# Aidan_Macro_Pad.net
KiCad netlist of a schematic drawn in Altium Designer
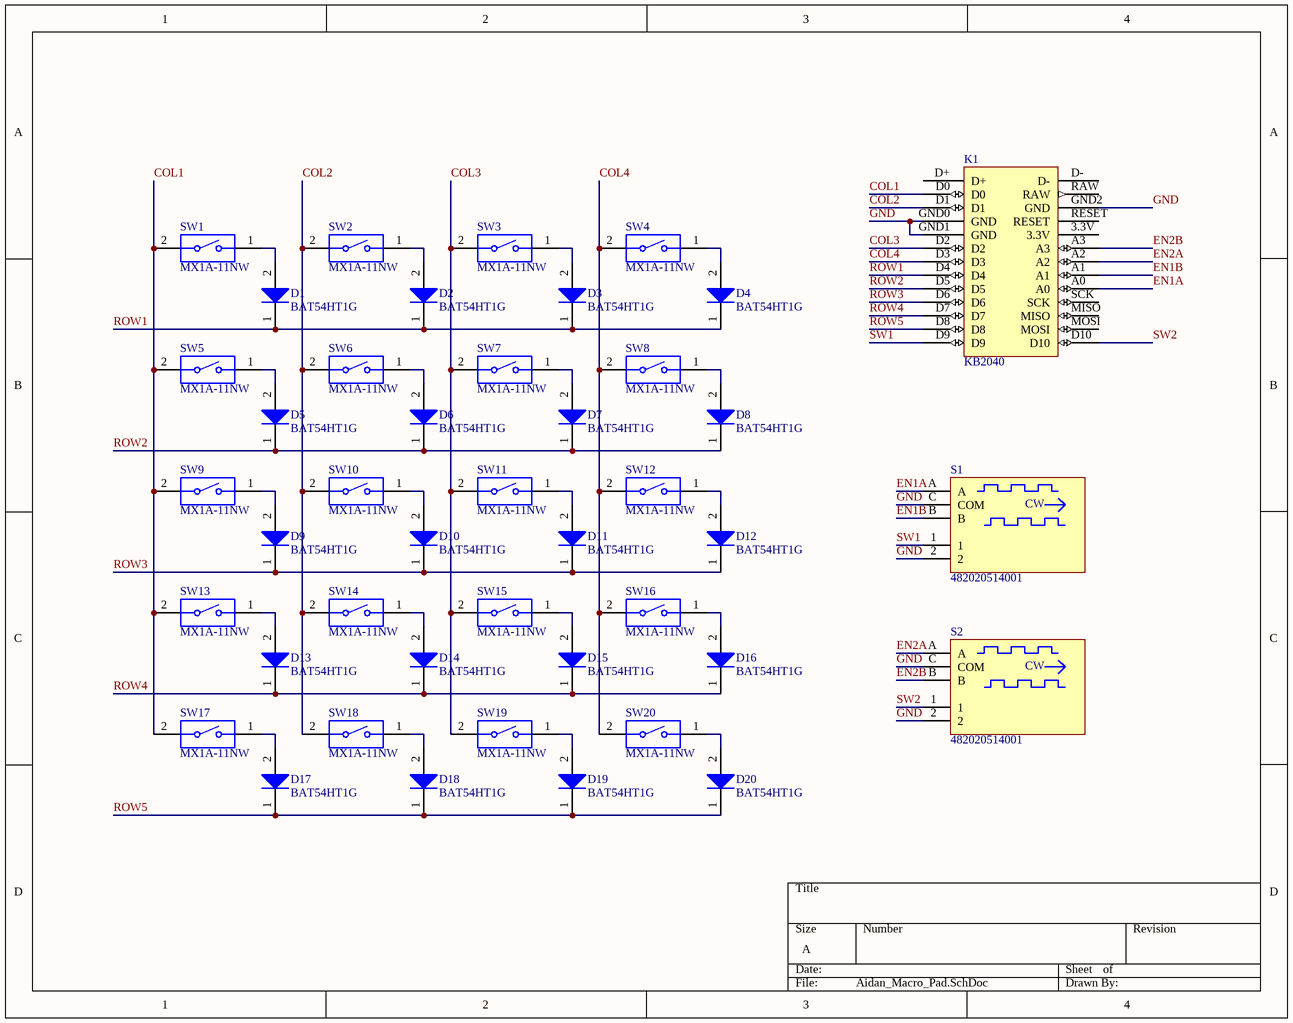
[diagram p0: Aidan_Macro_Pad.SchDoc]

(export (version "E")
  (design (tool "Eeschema 10.0.6"))
  (components
    (comp (ref "D1")
      (value "BAT54HT1G")
      (footprint "ONSC-SOD-323-2-477-02_V")
      (description "Rectifier Diode, 1 Phase, 1 Element, 0.2A, 30V V(RRM), Silicon")
      (libsource (lib "Aidan's Workspace") (part "ONSC-D-K1A2-2"))
    )
    (comp (ref "D2")
      (value "BAT54HT1G")
      (footprint "ONSC-SOD-323-2-477-02_V")
      (description "Rectifier Diode, 1 Phase, 1 Element, 0.2A, 30V V(RRM), Silicon")
      (libsource (lib "Aidan's Workspace") (part "ONSC-D-K1A2-2"))
    )
    (comp (ref "D3")
      (value "BAT54HT1G")
      (footprint "ONSC-SOD-323-2-477-02_V")
      (description "Rectifier Diode, 1 Phase, 1 Element, 0.2A, 30V V(RRM), Silicon")
      (libsource (lib "Aidan's Workspace") (part "ONSC-D-K1A2-2"))
    )
    (comp (ref "D4")
      (value "BAT54HT1G")
      (footprint "ONSC-SOD-323-2-477-02_V")
      (description "Rectifier Diode, 1 Phase, 1 Element, 0.2A, 30V V(RRM), Silicon")
      (libsource (lib "Aidan's Workspace") (part "ONSC-D-K1A2-2"))
    )
    (comp (ref "D5")
      (value "BAT54HT1G")
      (footprint "ONSC-SOD-323-2-477-02_V")
      (description "Rectifier Diode, 1 Phase, 1 Element, 0.2A, 30V V(RRM), Silicon")
      (libsource (lib "Aidan's Workspace") (part "ONSC-D-K1A2-2"))
    )
    (comp (ref "D6")
      (value "BAT54HT1G")
      (footprint "ONSC-SOD-323-2-477-02_V")
      (description "Rectifier Diode, 1 Phase, 1 Element, 0.2A, 30V V(RRM), Silicon")
      (libsource (lib "Aidan's Workspace") (part "ONSC-D-K1A2-2"))
    )
    (comp (ref "D7")
      (value "BAT54HT1G")
      (footprint "ONSC-SOD-323-2-477-02_V")
      (description "Rectifier Diode, 1 Phase, 1 Element, 0.2A, 30V V(RRM), Silicon")
      (libsource (lib "Aidan's Workspace") (part "ONSC-D-K1A2-2"))
    )
    (comp (ref "D8")
      (value "BAT54HT1G")
      (footprint "ONSC-SOD-323-2-477-02_V")
      (description "Rectifier Diode, 1 Phase, 1 Element, 0.2A, 30V V(RRM), Silicon")
      (libsource (lib "Aidan's Workspace") (part "ONSC-D-K1A2-2"))
    )
    (comp (ref "D9")
      (value "BAT54HT1G")
      (footprint "ONSC-SOD-323-2-477-02_V")
      (description "Rectifier Diode, 1 Phase, 1 Element, 0.2A, 30V V(RRM), Silicon")
      (libsource (lib "Aidan's Workspace") (part "ONSC-D-K1A2-2"))
    )
    (comp (ref "D10")
      (value "BAT54HT1G")
      (footprint "ONSC-SOD-323-2-477-02_V")
      (description "Rectifier Diode, 1 Phase, 1 Element, 0.2A, 30V V(RRM), Silicon")
      (libsource (lib "Aidan's Workspace") (part "ONSC-D-K1A2-2"))
    )
    (comp (ref "D11")
      (value "BAT54HT1G")
      (footprint "ONSC-SOD-323-2-477-02_V")
      (description "Rectifier Diode, 1 Phase, 1 Element, 0.2A, 30V V(RRM), Silicon")
      (libsource (lib "Aidan's Workspace") (part "ONSC-D-K1A2-2"))
    )
    (comp (ref "D12")
      (value "BAT54HT1G")
      (footprint "ONSC-SOD-323-2-477-02_V")
      (description "Rectifier Diode, 1 Phase, 1 Element, 0.2A, 30V V(RRM), Silicon")
      (libsource (lib "Aidan's Workspace") (part "ONSC-D-K1A2-2"))
    )
    (comp (ref "D13")
      (value "BAT54HT1G")
      (footprint "ONSC-SOD-323-2-477-02_V")
      (description "Rectifier Diode, 1 Phase, 1 Element, 0.2A, 30V V(RRM), Silicon")
      (libsource (lib "Aidan's Workspace") (part "ONSC-D-K1A2-2"))
    )
    (comp (ref "D14")
      (value "BAT54HT1G")
      (footprint "ONSC-SOD-323-2-477-02_V")
      (description "Rectifier Diode, 1 Phase, 1 Element, 0.2A, 30V V(RRM), Silicon")
      (libsource (lib "Aidan's Workspace") (part "ONSC-D-K1A2-2"))
    )
    (comp (ref "D15")
      (value "BAT54HT1G")
      (footprint "ONSC-SOD-323-2-477-02_V")
      (description "Rectifier Diode, 1 Phase, 1 Element, 0.2A, 30V V(RRM), Silicon")
      (libsource (lib "Aidan's Workspace") (part "ONSC-D-K1A2-2"))
    )
    (comp (ref "D16")
      (value "BAT54HT1G")
      (footprint "ONSC-SOD-323-2-477-02_V")
      (description "Rectifier Diode, 1 Phase, 1 Element, 0.2A, 30V V(RRM), Silicon")
      (libsource (lib "Aidan's Workspace") (part "ONSC-D-K1A2-2"))
    )
    (comp (ref "D17")
      (value "BAT54HT1G")
      (footprint "ONSC-SOD-323-2-477-02_V")
      (description "Rectifier Diode, 1 Phase, 1 Element, 0.2A, 30V V(RRM), Silicon")
      (libsource (lib "Aidan's Workspace") (part "ONSC-D-K1A2-2"))
    )
    (comp (ref "D18")
      (value "BAT54HT1G")
      (footprint "ONSC-SOD-323-2-477-02_V")
      (description "Rectifier Diode, 1 Phase, 1 Element, 0.2A, 30V V(RRM), Silicon")
      (libsource (lib "Aidan's Workspace") (part "ONSC-D-K1A2-2"))
    )
    (comp (ref "D19")
      (value "BAT54HT1G")
      (footprint "ONSC-SOD-323-2-477-02_V")
      (description "Rectifier Diode, 1 Phase, 1 Element, 0.2A, 30V V(RRM), Silicon")
      (libsource (lib "Aidan's Workspace") (part "ONSC-D-K1A2-2"))
    )
    (comp (ref "D20")
      (value "BAT54HT1G")
      (footprint "ONSC-SOD-323-2-477-02_V")
      (description "Rectifier Diode, 1 Phase, 1 Element, 0.2A, 30V V(RRM), Silicon")
      (libsource (lib "Aidan's Workspace") (part "ONSC-D-K1A2-2"))
    )
    (comp (ref "K1")
      (value "KB2040")
      (footprint "KB2040 Footprint")
      (description "Keyboard driver")
      (libsource (lib "Aidan's Workspace") (part "KB2040 Symbol"))
    )
    (comp (ref "S1")
      (value "482020514001")
      (footprint "4820xx514001")
      (description "Rotary Position Encoder")
      (libsource (lib "Aidan's Workspace") (part "Encoder Switch"))
    )
    (comp (ref "S2")
      (value "482020514001")
      (footprint "4820xx514001")
      (description "Rotary Position Encoder")
      (libsource (lib "Aidan's Workspace") (part "Encoder Switch"))
    )
    (comp (ref "SW1")
      (value "MX1A-11NW")
      (footprint "CHRY-MX1A-11NW_V")
      (libsource (lib "Aidan's Workspace") (part "KEYSW-SPST-2"))
    )
    (comp (ref "SW2")
      (value "MX1A-11NW")
      (footprint "CHRY-MX1A-11NW_V")
      (libsource (lib "Aidan's Workspace") (part "KEYSW-SPST-2"))
    )
    (comp (ref "SW3")
      (value "MX1A-11NW")
      (footprint "CHRY-MX1A-11NW_V")
      (libsource (lib "Aidan's Workspace") (part "KEYSW-SPST-2"))
    )
    (comp (ref "SW4")
      (value "MX1A-11NW")
      (footprint "CHRY-MX1A-11NW_V")
      (libsource (lib "Aidan's Workspace") (part "KEYSW-SPST-2"))
    )
    (comp (ref "SW5")
      (value "MX1A-11NW")
      (footprint "CHRY-MX1A-11NW_V")
      (libsource (lib "Aidan's Workspace") (part "KEYSW-SPST-2"))
    )
    (comp (ref "SW6")
      (value "MX1A-11NW")
      (footprint "CHRY-MX1A-11NW_V")
      (libsource (lib "Aidan's Workspace") (part "KEYSW-SPST-2"))
    )
    (comp (ref "SW7")
      (value "MX1A-11NW")
      (footprint "CHRY-MX1A-11NW_V")
      (libsource (lib "Aidan's Workspace") (part "KEYSW-SPST-2"))
    )
    (comp (ref "SW8")
      (value "MX1A-11NW")
      (footprint "CHRY-MX1A-11NW_V")
      (libsource (lib "Aidan's Workspace") (part "KEYSW-SPST-2"))
    )
    (comp (ref "SW9")
      (value "MX1A-11NW")
      (footprint "CHRY-MX1A-11NW_V")
      (libsource (lib "Aidan's Workspace") (part "KEYSW-SPST-2"))
    )
    (comp (ref "SW10")
      (value "MX1A-11NW")
      (footprint "CHRY-MX1A-11NW_V")
      (libsource (lib "Aidan's Workspace") (part "KEYSW-SPST-2"))
    )
    (comp (ref "SW11")
      (value "MX1A-11NW")
      (footprint "CHRY-MX1A-11NW_V")
      (libsource (lib "Aidan's Workspace") (part "KEYSW-SPST-2"))
    )
    (comp (ref "SW12")
      (value "MX1A-11NW")
      (footprint "CHRY-MX1A-11NW_V")
      (libsource (lib "Aidan's Workspace") (part "KEYSW-SPST-2"))
    )
    (comp (ref "SW13")
      (value "MX1A-11NW")
      (footprint "CHRY-MX1A-11NW_V")
      (libsource (lib "Aidan's Workspace") (part "KEYSW-SPST-2"))
    )
    (comp (ref "SW14")
      (value "MX1A-11NW")
      (footprint "CHRY-MX1A-11NW_V")
      (libsource (lib "Aidan's Workspace") (part "KEYSW-SPST-2"))
    )
    (comp (ref "SW15")
      (value "MX1A-11NW")
      (footprint "CHRY-MX1A-11NW_V")
      (libsource (lib "Aidan's Workspace") (part "KEYSW-SPST-2"))
    )
    (comp (ref "SW16")
      (value "MX1A-11NW")
      (footprint "CHRY-MX1A-11NW_V")
      (libsource (lib "Aidan's Workspace") (part "KEYSW-SPST-2"))
    )
    (comp (ref "SW17")
      (value "MX1A-11NW")
      (footprint "CHRY-MX1A-11NW_V")
      (libsource (lib "Aidan's Workspace") (part "KEYSW-SPST-2"))
    )
    (comp (ref "SW18")
      (value "MX1A-11NW")
      (footprint "CHRY-MX1A-11NW_V")
      (libsource (lib "Aidan's Workspace") (part "KEYSW-SPST-2"))
    )
    (comp (ref "SW19")
      (value "MX1A-11NW")
      (footprint "CHRY-MX1A-11NW_V")
      (libsource (lib "Aidan's Workspace") (part "KEYSW-SPST-2"))
    )
    (comp (ref "SW20")
      (value "MX1A-11NW")
      (footprint "CHRY-MX1A-11NW_V")
      (libsource (lib "Aidan's Workspace") (part "KEYSW-SPST-2"))
    )
  )
  (nets
    (net (code "1") (name "/COL1") (class "Default")
      (node (ref "K1") (pin "D0") (pinfunction "D0_D0") (pintype "bidirectional"))
      (node (ref "SW1") (pin "2") (pinfunction "2_2") (pintype "passive"))
      (node (ref "SW13") (pin "2") (pinfunction "2_2") (pintype "passive"))
      (node (ref "SW17") (pin "2") (pinfunction "2_2") (pintype "passive"))
      (node (ref "SW5") (pin "2") (pinfunction "2_2") (pintype "passive"))
      (node (ref "SW9") (pin "2") (pinfunction "2_2") (pintype "passive"))
    )
    (net (code "2") (name "/COL2") (class "Default")
      (node (ref "K1") (pin "D1") (pinfunction "D1_D1") (pintype "bidirectional"))
      (node (ref "SW10") (pin "2") (pinfunction "2_2") (pintype "passive"))
      (node (ref "SW14") (pin "2") (pinfunction "2_2") (pintype "passive"))
      (node (ref "SW18") (pin "2") (pinfunction "2_2") (pintype "passive"))
      (node (ref "SW2") (pin "2") (pinfunction "2_2") (pintype "passive"))
      (node (ref "SW6") (pin "2") (pinfunction "2_2") (pintype "passive"))
    )
    (net (code "3") (name "/COL3") (class "Default")
      (node (ref "K1") (pin "D2") (pinfunction "D2_D2") (pintype "bidirectional"))
      (node (ref "SW11") (pin "2") (pinfunction "2_2") (pintype "passive"))
      (node (ref "SW15") (pin "2") (pinfunction "2_2") (pintype "passive"))
      (node (ref "SW19") (pin "2") (pinfunction "2_2") (pintype "passive"))
      (node (ref "SW3") (pin "2") (pinfunction "2_2") (pintype "passive"))
      (node (ref "SW7") (pin "2") (pinfunction "2_2") (pintype "passive"))
    )
    (net (code "4") (name "/COL4") (class "Default")
      (node (ref "K1") (pin "D3") (pinfunction "D3_D3") (pintype "bidirectional"))
      (node (ref "SW12") (pin "2") (pinfunction "2_2") (pintype "passive"))
      (node (ref "SW16") (pin "2") (pinfunction "2_2") (pintype "passive"))
      (node (ref "SW20") (pin "2") (pinfunction "2_2") (pintype "passive"))
      (node (ref "SW4") (pin "2") (pinfunction "2_2") (pintype "passive"))
      (node (ref "SW8") (pin "2") (pinfunction "2_2") (pintype "passive"))
    )
    (net (code "5") (name "/EN1A") (class "Default")
      (node (ref "K1") (pin "A0") (pinfunction "A0_A0") (pintype "bidirectional"))
      (node (ref "S1") (pin "A") (pinfunction "A_A") (pintype "passive"))
    )
    (net (code "6") (name "/EN1B") (class "Default")
      (node (ref "K1") (pin "A1") (pinfunction "A1_A1") (pintype "bidirectional"))
      (node (ref "S1") (pin "B") (pinfunction "B_B") (pintype "passive"))
    )
    (net (code "7") (name "/EN2A") (class "Default")
      (node (ref "K1") (pin "A2") (pinfunction "A2_A2") (pintype "bidirectional"))
      (node (ref "S2") (pin "A") (pinfunction "A_A") (pintype "passive"))
    )
    (net (code "8") (name "/EN2B") (class "Default")
      (node (ref "K1") (pin "A3") (pinfunction "A3_A3") (pintype "bidirectional"))
      (node (ref "S2") (pin "B") (pinfunction "B_B") (pintype "passive"))
    )
    (net (code "9") (name "/GND") (class "Default")
      (node (ref "K1") (pin "GND0") (pinfunction "GND_GND0") (pintype "power_in"))
      (node (ref "K1") (pin "GND1") (pinfunction "GND_GND1") (pintype "power_in"))
      (node (ref "K1") (pin "GND2") (pinfunction "GND_GND2") (pintype "power_in"))
      (node (ref "S1") (pin "2") (pinfunction "2_2") (pintype "passive"))
      (node (ref "S1") (pin "C") (pinfunction "COM_C") (pintype "passive"))
      (node (ref "S2") (pin "2") (pinfunction "2_2") (pintype "passive"))
      (node (ref "S2") (pin "C") (pinfunction "COM_C") (pintype "passive"))
    )
    (net (code "10") (name "/ROW1") (class "Default")
      (node (ref "D1") (pin "1") (pinfunction "K_1") (pintype "passive"))
      (node (ref "D2") (pin "1") (pinfunction "K_1") (pintype "passive"))
      (node (ref "D3") (pin "1") (pinfunction "K_1") (pintype "passive"))
      (node (ref "D4") (pin "1") (pinfunction "K_1") (pintype "passive"))
      (node (ref "K1") (pin "D4") (pinfunction "D4_D4") (pintype "bidirectional"))
    )
    (net (code "11") (name "/ROW2") (class "Default")
      (node (ref "D5") (pin "1") (pinfunction "K_1") (pintype "passive"))
      (node (ref "D6") (pin "1") (pinfunction "K_1") (pintype "passive"))
      (node (ref "D7") (pin "1") (pinfunction "K_1") (pintype "passive"))
      (node (ref "D8") (pin "1") (pinfunction "K_1") (pintype "passive"))
      (node (ref "K1") (pin "D5") (pinfunction "D5_D5") (pintype "bidirectional"))
    )
    (net (code "12") (name "/ROW3") (class "Default")
      (node (ref "D10") (pin "1") (pinfunction "K_1") (pintype "passive"))
      (node (ref "D11") (pin "1") (pinfunction "K_1") (pintype "passive"))
      (node (ref "D12") (pin "1") (pinfunction "K_1") (pintype "passive"))
      (node (ref "D9") (pin "1") (pinfunction "K_1") (pintype "passive"))
      (node (ref "K1") (pin "D6") (pinfunction "D6_D6") (pintype "bidirectional"))
    )
    (net (code "13") (name "/ROW4") (class "Default")
      (node (ref "D13") (pin "1") (pinfunction "K_1") (pintype "passive"))
      (node (ref "D14") (pin "1") (pinfunction "K_1") (pintype "passive"))
      (node (ref "D15") (pin "1") (pinfunction "K_1") (pintype "passive"))
      (node (ref "D16") (pin "1") (pinfunction "K_1") (pintype "passive"))
      (node (ref "K1") (pin "D7") (pinfunction "D7_D7") (pintype "bidirectional"))
    )
    (net (code "14") (name "/ROW5") (class "Default")
      (node (ref "D17") (pin "1") (pinfunction "K_1") (pintype "passive"))
      (node (ref "D18") (pin "1") (pinfunction "K_1") (pintype "passive"))
      (node (ref "D19") (pin "1") (pinfunction "K_1") (pintype "passive"))
      (node (ref "D20") (pin "1") (pinfunction "K_1") (pintype "passive"))
      (node (ref "K1") (pin "D8") (pinfunction "D8_D8") (pintype "bidirectional"))
    )
    (net (code "15") (name "/SW1") (class "Default")
      (node (ref "K1") (pin "D9") (pinfunction "D9_D9") (pintype "bidirectional"))
      (node (ref "S1") (pin "1") (pinfunction "1_1") (pintype "passive"))
    )
    (net (code "16") (name "/SW2") (class "Default")
      (node (ref "K1") (pin "D10") (pinfunction "D10_D10") (pintype "bidirectional"))
      (node (ref "S2") (pin "1") (pinfunction "1_1") (pintype "passive"))
    )
    (net (code "17") (name "Net-(D1-A)") (class "Default")
      (node (ref "D1") (pin "2") (pinfunction "A_2") (pintype "passive"))
      (node (ref "SW1") (pin "1") (pinfunction "1_1") (pintype "passive"))
    )
    (net (code "18") (name "Net-(D2-A)") (class "Default")
      (node (ref "D2") (pin "2") (pinfunction "A_2") (pintype "passive"))
      (node (ref "SW2") (pin "1") (pinfunction "1_1") (pintype "passive"))
    )
    (net (code "19") (name "Net-(D3-A)") (class "Default")
      (node (ref "D3") (pin "2") (pinfunction "A_2") (pintype "passive"))
      (node (ref "SW3") (pin "1") (pinfunction "1_1") (pintype "passive"))
    )
    (net (code "20") (name "Net-(D4-A)") (class "Default")
      (node (ref "D4") (pin "2") (pinfunction "A_2") (pintype "passive"))
      (node (ref "SW4") (pin "1") (pinfunction "1_1") (pintype "passive"))
    )
    (net (code "21") (name "Net-(D5-A)") (class "Default")
      (node (ref "D5") (pin "2") (pinfunction "A_2") (pintype "passive"))
      (node (ref "SW5") (pin "1") (pinfunction "1_1") (pintype "passive"))
    )
    (net (code "22") (name "Net-(D6-A)") (class "Default")
      (node (ref "D6") (pin "2") (pinfunction "A_2") (pintype "passive"))
      (node (ref "SW6") (pin "1") (pinfunction "1_1") (pintype "passive"))
    )
    (net (code "23") (name "Net-(D7-A)") (class "Default")
      (node (ref "D7") (pin "2") (pinfunction "A_2") (pintype "passive"))
      (node (ref "SW7") (pin "1") (pinfunction "1_1") (pintype "passive"))
    )
    (net (code "24") (name "Net-(D8-A)") (class "Default")
      (node (ref "D8") (pin "2") (pinfunction "A_2") (pintype "passive"))
      (node (ref "SW8") (pin "1") (pinfunction "1_1") (pintype "passive"))
    )
    (net (code "25") (name "Net-(D9-A)") (class "Default")
      (node (ref "D9") (pin "2") (pinfunction "A_2") (pintype "passive"))
      (node (ref "SW9") (pin "1") (pinfunction "1_1") (pintype "passive"))
    )
    (net (code "26") (name "Net-(D10-A)") (class "Default")
      (node (ref "D10") (pin "2") (pinfunction "A_2") (pintype "passive"))
      (node (ref "SW10") (pin "1") (pinfunction "1_1") (pintype "passive"))
    )
    (net (code "27") (name "Net-(D11-A)") (class "Default")
      (node (ref "D11") (pin "2") (pinfunction "A_2") (pintype "passive"))
      (node (ref "SW11") (pin "1") (pinfunction "1_1") (pintype "passive"))
    )
    (net (code "28") (name "Net-(D12-A)") (class "Default")
      (node (ref "D12") (pin "2") (pinfunction "A_2") (pintype "passive"))
      (node (ref "SW12") (pin "1") (pinfunction "1_1") (pintype "passive"))
    )
    (net (code "29") (name "Net-(D13-A)") (class "Default")
      (node (ref "D13") (pin "2") (pinfunction "A_2") (pintype "passive"))
      (node (ref "SW13") (pin "1") (pinfunction "1_1") (pintype "passive"))
    )
    (net (code "30") (name "Net-(D14-A)") (class "Default")
      (node (ref "D14") (pin "2") (pinfunction "A_2") (pintype "passive"))
      (node (ref "SW14") (pin "1") (pinfunction "1_1") (pintype "passive"))
    )
    (net (code "31") (name "Net-(D15-A)") (class "Default")
      (node (ref "D15") (pin "2") (pinfunction "A_2") (pintype "passive"))
      (node (ref "SW15") (pin "1") (pinfunction "1_1") (pintype "passive"))
    )
    (net (code "32") (name "Net-(D16-A)") (class "Default")
      (node (ref "D16") (pin "2") (pinfunction "A_2") (pintype "passive"))
      (node (ref "SW16") (pin "1") (pinfunction "1_1") (pintype "passive"))
    )
    (net (code "33") (name "Net-(D17-A)") (class "Default")
      (node (ref "D17") (pin "2") (pinfunction "A_2") (pintype "passive"))
      (node (ref "SW17") (pin "1") (pinfunction "1_1") (pintype "passive"))
    )
    (net (code "34") (name "Net-(D18-A)") (class "Default")
      (node (ref "D18") (pin "2") (pinfunction "A_2") (pintype "passive"))
      (node (ref "SW18") (pin "1") (pinfunction "1_1") (pintype "passive"))
    )
    (net (code "35") (name "Net-(D19-A)") (class "Default")
      (node (ref "D19") (pin "2") (pinfunction "A_2") (pintype "passive"))
      (node (ref "SW19") (pin "1") (pinfunction "1_1") (pintype "passive"))
    )
    (net (code "36") (name "Net-(D20-A)") (class "Default")
      (node (ref "D20") (pin "2") (pinfunction "A_2") (pintype "passive"))
      (node (ref "SW20") (pin "1") (pinfunction "1_1") (pintype "passive"))
    )
    (net (code "37") (name "unconnected-(K1-Pad3.3V)") (class "Default")
      (node (ref "K1") (pin "3.3V") (pinfunction "3.3V_3.3V") (pintype "power_in"))
    )
    (net (code "38") (name "unconnected-(K1-PadD+)") (class "Default")
      (node (ref "K1") (pin "D+") (pinfunction "D+_D+") (pintype "passive"))
    )
    (net (code "39") (name "unconnected-(K1-PadD-)") (class "Default")
      (node (ref "K1") (pin "D-") (pinfunction "D-_D-") (pintype "passive"))
    )
    (net (code "40") (name "unconnected-(K1-PadMISO)") (class "Default")
      (node (ref "K1") (pin "MISO") (pinfunction "MISO_MISO") (pintype "bidirectional"))
    )
    (net (code "41") (name "unconnected-(K1-PadMOSI)") (class "Default")
      (node (ref "K1") (pin "MOSI") (pinfunction "MOSI_MOSI") (pintype "bidirectional"))
    )
    (net (code "42") (name "unconnected-(K1-PadRAW)") (class "Default")
      (node (ref "K1") (pin "RAW") (pinfunction "RAW_RAW") (pintype "output"))
    )
    (net (code "43") (name "unconnected-(K1-PadRESET)") (class "Default")
      (node (ref "K1") (pin "RESET") (pinfunction "RESET_RESET") (pintype "passive"))
    )
    (net (code "44") (name "unconnected-(K1-PadSCK)") (class "Default")
      (node (ref "K1") (pin "SCK") (pinfunction "SCK_SCK") (pintype "bidirectional"))
    )
  )
)
